# Sheet1.net
KiCad netlist of a schematic drawn in Altium Designer
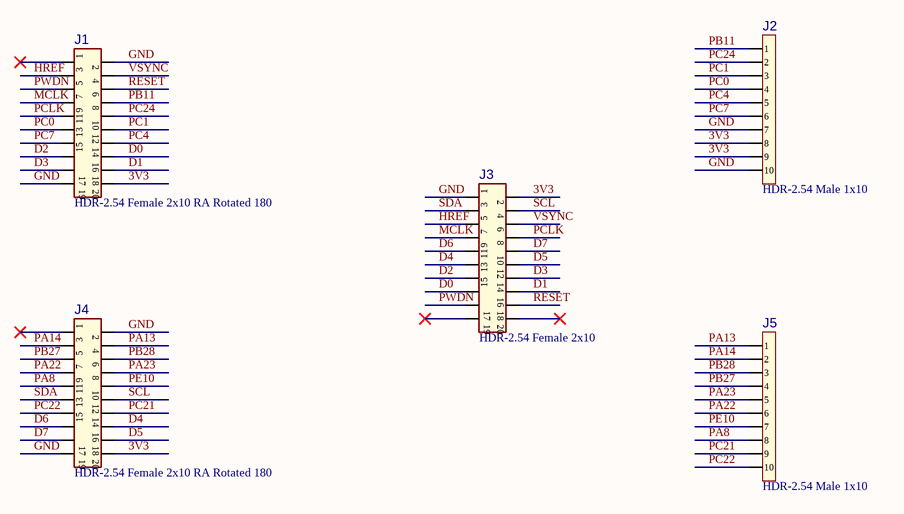
[diagram p0: Sheet1.SchDoc]

(export (version "E")
  (design (tool "Eeschema 10.0.6"))
  (components
    (comp (ref "J1")
      (value "HDR-2.54 Female 2x10 RA Rotated 180")
      (footprint "HDR_F_2.54_2x10_RA_180")
      (fields (field (name "Comment") "Header 2x10") (field (name "OWNER") "Jamus Griego"))
      (libsource (lib "MCHP-CDB") (part "Header 2x10"))
    )
    (comp (ref "J2")
      (value "HDR-2.54 Male 1x10")
      (footprint "HDR_M_2.54_1x10")
      (fields (field (name "Comment") "Header 1x10"))
      (libsource (lib "MCHP-CDB") (part "Header 1x10"))
    )
    (comp (ref "J3")
      (value "HDR-2.54 Female 2x10")
      (footprint "HDR_F_2.54_2x10_SFH11-PBPC-D10-ST-BK")
      (fields
        (field (name "VOLTAGE") "1000VAC")
        (field (name "Comment") "Header 2x10")
        (field (name "OWNER") "Dragos Danaila")
      )
      (libsource (lib "MCHP-CDB") (part "Header 2x10"))
    )
    (comp (ref "J4")
      (value "HDR-2.54 Female 2x10 RA Rotated 180")
      (footprint "HDR_F_2.54_2x10_RA_180")
      (fields (field (name "Comment") "Header 2x10") (field (name "OWNER") "Jamus Griego"))
      (libsource (lib "MCHP-CDB") (part "Header 2x10"))
    )
    (comp (ref "J5")
      (value "HDR-2.54 Male 1x10")
      (footprint "HDR_M_2.54_1x10")
      (fields (field (name "Comment") "Header 1x10"))
      (libsource (lib "MCHP-CDB") (part "Header 1x10"))
    )
  )
  (nets
    (net (code "1") (name "/3V3") (class "Default")
      (node (ref "J1") (pin "20") (pinfunction "20_20") (pintype "passive"))
      (node (ref "J2") (pin "8") (pinfunction "8_8") (pintype "passive"))
      (node (ref "J2") (pin "9") (pinfunction "9_9") (pintype "passive"))
      (node (ref "J3") (pin "2") (pinfunction "2_2") (pintype "passive"))
      (node (ref "J4") (pin "20") (pinfunction "20_20") (pintype "passive"))
    )
    (net (code "2") (name "/D0") (class "Default")
      (node (ref "J1") (pin "16") (pinfunction "16_16") (pintype "passive"))
      (node (ref "J3") (pin "15") (pinfunction "15_15") (pintype "passive"))
    )
    (net (code "3") (name "/D1") (class "Default")
      (node (ref "J1") (pin "18") (pinfunction "18_18") (pintype "passive"))
      (node (ref "J3") (pin "16") (pinfunction "16_16") (pintype "passive"))
    )
    (net (code "4") (name "/D2") (class "Default")
      (node (ref "J1") (pin "15") (pinfunction "15_15") (pintype "passive"))
      (node (ref "J3") (pin "13") (pinfunction "13_13") (pintype "passive"))
    )
    (net (code "5") (name "/D3") (class "Default")
      (node (ref "J1") (pin "17") (pinfunction "17_17") (pintype "passive"))
      (node (ref "J3") (pin "14") (pinfunction "14_14") (pintype "passive"))
    )
    (net (code "6") (name "/D4") (class "Default")
      (node (ref "J3") (pin "11") (pinfunction "11_11") (pintype "passive"))
      (node (ref "J4") (pin "16") (pinfunction "16_16") (pintype "passive"))
    )
    (net (code "7") (name "/D5") (class "Default")
      (node (ref "J3") (pin "12") (pinfunction "12_12") (pintype "passive"))
      (node (ref "J4") (pin "18") (pinfunction "18_18") (pintype "passive"))
    )
    (net (code "8") (name "/D6") (class "Default")
      (node (ref "J3") (pin "9") (pinfunction "9_9") (pintype "passive"))
      (node (ref "J4") (pin "15") (pinfunction "15_15") (pintype "passive"))
    )
    (net (code "9") (name "/D7") (class "Default")
      (node (ref "J3") (pin "10") (pinfunction "10_10") (pintype "passive"))
      (node (ref "J4") (pin "17") (pinfunction "17_17") (pintype "passive"))
    )
    (net (code "10") (name "/GND") (class "Default")
      (node (ref "J1") (pin "19") (pinfunction "19_19") (pintype "passive"))
      (node (ref "J1") (pin "2") (pinfunction "2_2") (pintype "passive"))
      (node (ref "J2") (pin "10") (pinfunction "10_10") (pintype "passive"))
      (node (ref "J2") (pin "7") (pinfunction "7_7") (pintype "passive"))
      (node (ref "J3") (pin "1") (pinfunction "1_1") (pintype "passive"))
      (node (ref "J4") (pin "19") (pinfunction "19_19") (pintype "passive"))
      (node (ref "J4") (pin "2") (pinfunction "2_2") (pintype "passive"))
    )
    (net (code "11") (name "/HREF") (class "Default")
      (node (ref "J1") (pin "3") (pinfunction "3_3") (pintype "passive"))
      (node (ref "J3") (pin "5") (pinfunction "5_5") (pintype "passive"))
    )
    (net (code "12") (name "/MCLK") (class "Default")
      (node (ref "J1") (pin "7") (pinfunction "7_7") (pintype "passive"))
      (node (ref "J3") (pin "7") (pinfunction "7_7") (pintype "passive"))
    )
    (net (code "13") (name "/PA8") (class "Default")
      (node (ref "J4") (pin "9") (pinfunction "9_9") (pintype "passive"))
      (node (ref "J5") (pin "8") (pinfunction "8_8") (pintype "passive"))
    )
    (net (code "14") (name "/PA13") (class "Default")
      (node (ref "J4") (pin "4") (pinfunction "4_4") (pintype "passive"))
      (node (ref "J5") (pin "1") (pinfunction "1_1") (pintype "passive"))
    )
    (net (code "15") (name "/PA14") (class "Default")
      (node (ref "J4") (pin "3") (pinfunction "3_3") (pintype "passive"))
      (node (ref "J5") (pin "2") (pinfunction "2_2") (pintype "passive"))
    )
    (net (code "16") (name "/PA22") (class "Default")
      (node (ref "J4") (pin "7") (pinfunction "7_7") (pintype "passive"))
      (node (ref "J5") (pin "6") (pinfunction "6_6") (pintype "passive"))
    )
    (net (code "17") (name "/PA23") (class "Default")
      (node (ref "J4") (pin "8") (pinfunction "8_8") (pintype "passive"))
      (node (ref "J5") (pin "5") (pinfunction "5_5") (pintype "passive"))
    )
    (net (code "18") (name "/PB11") (class "Default")
      (node (ref "J1") (pin "8") (pinfunction "8_8") (pintype "passive"))
      (node (ref "J2") (pin "1") (pinfunction "1_1") (pintype "passive"))
    )
    (net (code "19") (name "/PB27") (class "Default")
      (node (ref "J4") (pin "5") (pinfunction "5_5") (pintype "passive"))
      (node (ref "J5") (pin "4") (pinfunction "4_4") (pintype "passive"))
    )
    (net (code "20") (name "/PB28") (class "Default")
      (node (ref "J4") (pin "6") (pinfunction "6_6") (pintype "passive"))
      (node (ref "J5") (pin "3") (pinfunction "3_3") (pintype "passive"))
    )
    (net (code "21") (name "/PC0") (class "Default")
      (node (ref "J1") (pin "11") (pinfunction "11_11") (pintype "passive"))
      (node (ref "J2") (pin "4") (pinfunction "4_4") (pintype "passive"))
    )
    (net (code "22") (name "/PC1") (class "Default")
      (node (ref "J1") (pin "12") (pinfunction "12_12") (pintype "passive"))
      (node (ref "J2") (pin "3") (pinfunction "3_3") (pintype "passive"))
    )
    (net (code "23") (name "/PC4") (class "Default")
      (node (ref "J1") (pin "14") (pinfunction "14_14") (pintype "passive"))
      (node (ref "J2") (pin "5") (pinfunction "5_5") (pintype "passive"))
    )
    (net (code "24") (name "/PC7") (class "Default")
      (node (ref "J1") (pin "13") (pinfunction "13_13") (pintype "passive"))
      (node (ref "J2") (pin "6") (pinfunction "6_6") (pintype "passive"))
    )
    (net (code "25") (name "/PC21") (class "Default")
      (node (ref "J4") (pin "14") (pinfunction "14_14") (pintype "passive"))
      (node (ref "J5") (pin "9") (pinfunction "9_9") (pintype "passive"))
    )
    (net (code "26") (name "/PC22") (class "Default")
      (node (ref "J4") (pin "13") (pinfunction "13_13") (pintype "passive"))
      (node (ref "J5") (pin "10") (pinfunction "10_10") (pintype "passive"))
    )
    (net (code "27") (name "/PC24") (class "Default")
      (node (ref "J1") (pin "10") (pinfunction "10_10") (pintype "passive"))
      (node (ref "J2") (pin "2") (pinfunction "2_2") (pintype "passive"))
    )
    (net (code "28") (name "/PCLK") (class "Default")
      (node (ref "J1") (pin "9") (pinfunction "9_9") (pintype "passive"))
      (node (ref "J3") (pin "8") (pinfunction "8_8") (pintype "passive"))
    )
    (net (code "29") (name "/PE10") (class "Default")
      (node (ref "J4") (pin "10") (pinfunction "10_10") (pintype "passive"))
      (node (ref "J5") (pin "7") (pinfunction "7_7") (pintype "passive"))
    )
    (net (code "30") (name "/PWDN") (class "Default")
      (node (ref "J1") (pin "5") (pinfunction "5_5") (pintype "passive"))
      (node (ref "J3") (pin "17") (pinfunction "17_17") (pintype "passive"))
    )
    (net (code "31") (name "/RESET") (class "Default")
      (node (ref "J1") (pin "6") (pinfunction "6_6") (pintype "passive"))
      (node (ref "J3") (pin "18") (pinfunction "18_18") (pintype "passive"))
    )
    (net (code "32") (name "/SCL") (class "Default")
      (node (ref "J3") (pin "4") (pinfunction "4_4") (pintype "passive"))
      (node (ref "J4") (pin "12") (pinfunction "12_12") (pintype "passive"))
    )
    (net (code "33") (name "/SDA") (class "Default")
      (node (ref "J3") (pin "3") (pinfunction "3_3") (pintype "passive"))
      (node (ref "J4") (pin "11") (pinfunction "11_11") (pintype "passive"))
    )
    (net (code "34") (name "/VSYNC") (class "Default")
      (node (ref "J1") (pin "4") (pinfunction "4_4") (pintype "passive"))
      (node (ref "J3") (pin "6") (pinfunction "6_6") (pintype "passive"))
    )
    (net (code "35") (name "unconnected-(J1-Pad1)") (class "Default")
      (node (ref "J1") (pin "1") (pinfunction "1_1") (pintype "passive+no_connect"))
    )
    (net (code "36") (name "unconnected-(J3-Pad19)") (class "Default")
      (node (ref "J3") (pin "19") (pinfunction "19_19") (pintype "passive+no_connect"))
    )
    (net (code "37") (name "unconnected-(J3-Pad20)") (class "Default")
      (node (ref "J3") (pin "20") (pinfunction "20_20") (pintype "passive+no_connect"))
    )
    (net (code "38") (name "unconnected-(J4-Pad1)") (class "Default")
      (node (ref "J4") (pin "1") (pinfunction "1_1") (pintype "passive+no_connect"))
    )
  )
)
